# Sheet1.net
KiCad netlist of a schematic drawn in Altium Designer
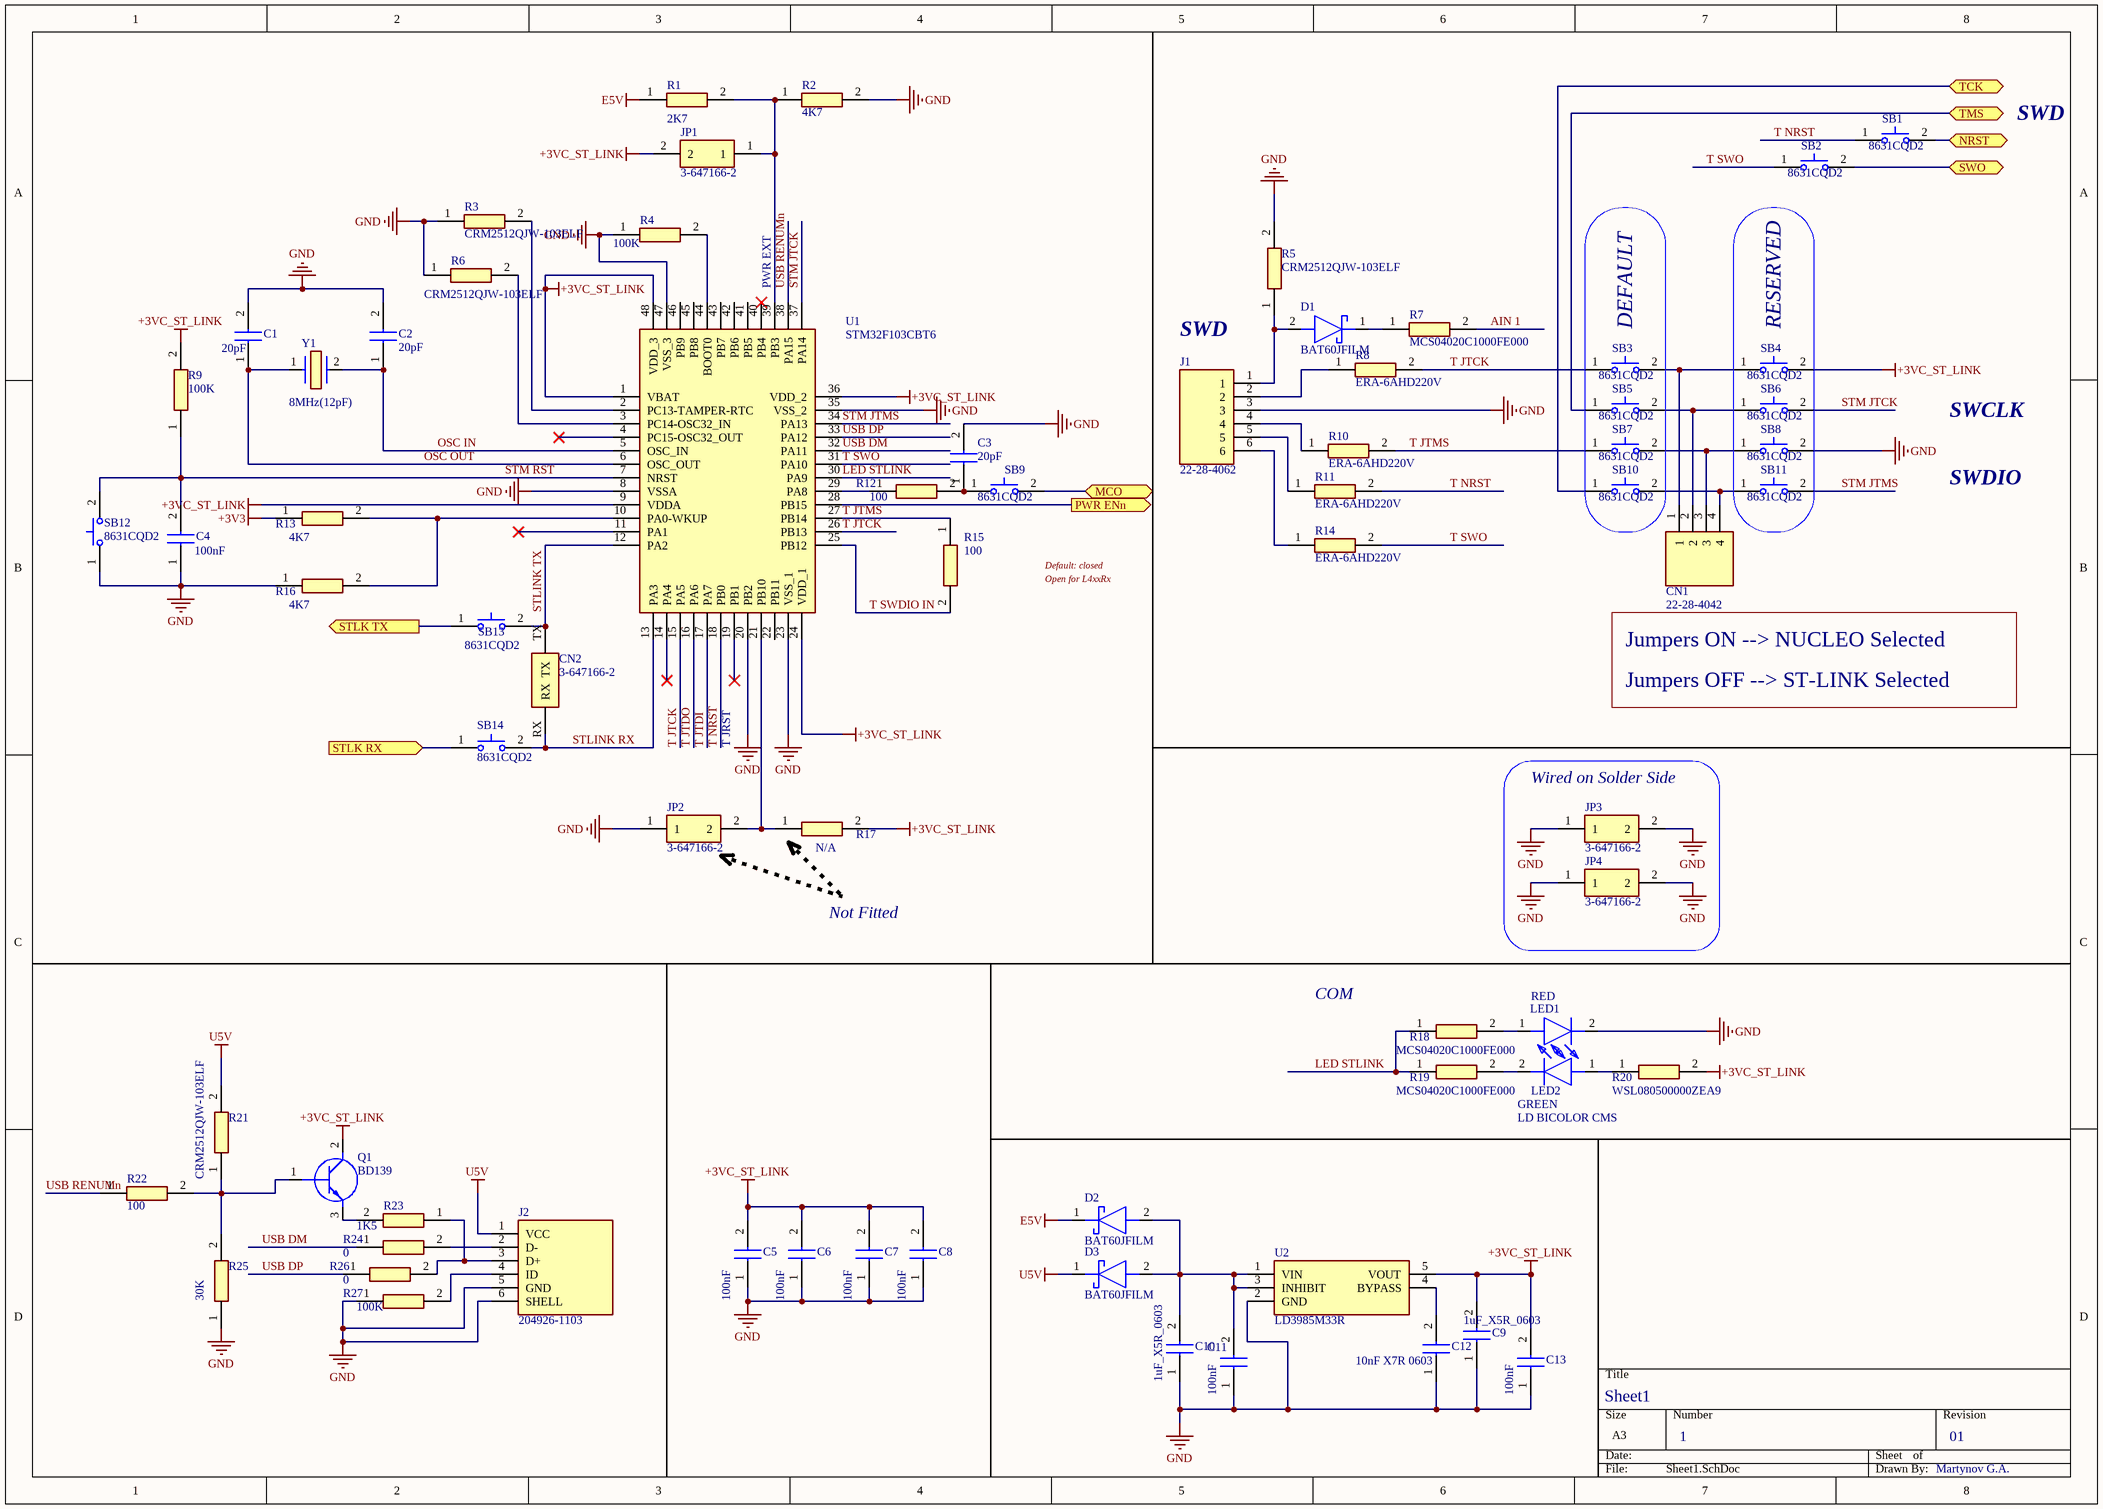
[diagram p0: Sheet1.SchDoc]

(export (version "E")
  (design (tool "Eeschema 10.0.6"))
  (components
    (comp (ref "C1")
      (value "20pF")
      (footprint "SamacSys:C1206")
      (description "Capacitor")
      (fields (field (name "MANUFACTURER_PART_NUMBER") "C1206C200KCGACTU"))
      (libsource (lib "*") (part "C1206C200KCGACTU"))
    )
    (comp (ref "C2")
      (value "20pF")
      (footprint "SamacSys:C1206")
      (description "Capacitor")
      (fields (field (name "MANUFACTURER_PART_NUMBER") "C1206C200KCGACTU"))
      (libsource (lib "*") (part "C1206C200KCGACTU"))
    )
    (comp (ref "C3")
      (value "20pF")
      (footprint "SamacSys:C1206")
      (description "Capacitor")
      (fields (field (name "MANUFACTURER_PART_NUMBER") "C1206C200KCGACTU"))
      (libsource (lib "*") (part "C1206C200KCGACTU"))
    )
    (comp (ref "C4")
      (value "100nF")
      (footprint "SamacSys:CAPC1608X90N")
      (description "Capacitor")
      (fields
        (field (name "MANUFACTURER_PART_NUMBER") "06035C104K4T4A")
        (field (name "MOUSER PART NUMBER") "581-06035C104K4T4A")
      )
      (libsource (lib "*") (part "06035C104K4T4A"))
    )
    (comp (ref "C5")
      (value "100nF")
      (footprint "SamacSys:CAPC1608X90N")
      (description "Capacitor")
      (fields
        (field (name "MANUFACTURER_PART_NUMBER") "06035C104K4T4A")
        (field (name "MOUSER PART NUMBER") "581-06035C104K4T4A")
      )
      (libsource (lib "*") (part "06035C104K4T4A"))
    )
    (comp (ref "C6")
      (value "100nF")
      (footprint "SamacSys:CAPC1608X90N")
      (description "Capacitor")
      (fields
        (field (name "MANUFACTURER_PART_NUMBER") "06035C104K4T4A")
        (field (name "MOUSER PART NUMBER") "581-06035C104K4T4A")
      )
      (libsource (lib "*") (part "06035C104K4T4A"))
    )
    (comp (ref "C7")
      (value "100nF")
      (footprint "SamacSys:CAPC1608X90N")
      (description "Capacitor")
      (fields
        (field (name "MANUFACTURER_PART_NUMBER") "06035C104K4T4A")
        (field (name "MOUSER PART NUMBER") "581-06035C104K4T4A")
      )
      (libsource (lib "*") (part "06035C104K4T4A"))
    )
    (comp (ref "C8")
      (value "100nF")
      (footprint "SamacSys:CAPC1608X90N")
      (description "Capacitor")
      (fields
        (field (name "MANUFACTURER_PART_NUMBER") "06035C104K4T4A")
        (field (name "MOUSER PART NUMBER") "581-06035C104K4T4A")
      )
      (libsource (lib "*") (part "06035C104K4T4A"))
    )
    (comp (ref "C9")
      (value "1uF_X5R_0603")
      (footprint "SamacSys:MAJx16")
      (description "Capacitor")
      (fields (field (name "MANUFACTURER_PART_NUMBER") "MAJCT168BB7105KTEA01"))
      (libsource (lib "*") (part "MAJCT168BB7105KTEA01"))
    )
    (comp (ref "C10")
      (value "1uF_X5R_0603")
      (footprint "SamacSys:MAJx16")
      (description "Capacitor")
      (fields (field (name "MANUFACTURER_PART_NUMBER") "MAJCT168BB7105KTEA01"))
      (libsource (lib "*") (part "MAJCT168BB7105KTEA01"))
    )
    (comp (ref "C11")
      (value "100nF")
      (footprint "SamacSys:CAPC1608X90N")
      (description "Capacitor")
      (fields
        (field (name "MANUFACTURER_PART_NUMBER") "06035C104K4T4A")
        (field (name "MOUSER PART NUMBER") "581-06035C104K4T4A")
      )
      (libsource (lib "*") (part "06035C104K4T4A"))
    )
    (comp (ref "C12")
      (value "10nF X7R 0603")
      (footprint "SamacSys:CAPC3316X145N")
      (description "Capacitor")
      (fields
        (field (name "MANUFACTURER_PART_NUMBER") "KGM31GCG2J103JU")
        (field (name "MOUSER PART NUMBER") "581-KGM31GCG2J103JU")
      )
      (libsource (lib "*") (part "KGM31GCG2J103JU"))
    )
    (comp (ref "C13")
      (value "100nF")
      (footprint "SamacSys:CAPC1608X90N")
      (description "Capacitor")
      (fields
        (field (name "MANUFACTURER_PART_NUMBER") "06035C104K4T4A")
        (field (name "MOUSER PART NUMBER") "581-06035C104K4T4A")
      )
      (libsource (lib "*") (part "06035C104K4T4A"))
    )
    (comp (ref "CN1")
      (value "22-28-4042")
      (footprint "SamacSys:HDRV4W66P0X254_1X4_1016X249X1003P")
      (description "Connector")
      (fields (field (name "MOUSER PART NUMBER") "538-22-28-4042"))
      (libsource (lib "*") (part "22-28-4042"))
    )
    (comp (ref "CN2")
      (value "3-647166-2")
      (footprint "SamacSys:36471662")
      (description "Connector")
      (fields (field (name "MOUSER PART NUMBER") "571-3-647166-2"))
      (libsource (lib "") (part "3-647166-2_2"))
    )
    (comp (ref "D1")
      (value "BAT60JFILM")
      (footprint "SamacSys:SOD2513X117N")
      (description "Schottky Diode")
      (fields (field (name "MOUSER PART NUMBER") "511-BAT60JFILM"))
      (libsource (lib "*") (part "BAT60JFILM"))
    )
    (comp (ref "D2")
      (value "BAT60JFILM")
      (footprint "SamacSys:SOD2513X117N")
      (description "Schottky Diode")
      (fields (field (name "MOUSER PART NUMBER") "511-BAT60JFILM"))
      (libsource (lib "*") (part "BAT60JFILM"))
    )
    (comp (ref "D3")
      (value "BAT60JFILM")
      (footprint "SamacSys:SOD2513X117N")
      (description "Schottky Diode")
      (fields (field (name "MOUSER PART NUMBER") "511-BAT60JFILM"))
      (libsource (lib "*") (part "BAT60JFILM"))
    )
    (comp (ref "J1")
      (value "22-28-4062")
      (footprint "SamacSys:HDRV6W66P0X254_1X6_1524X249X838P")
      (description "Connector")
      (fields (field (name "MOUSER PART NUMBER") "538-22-28-4062"))
      (libsource (lib "*") (part "22-28-4062"))
    )
    (comp (ref "J2")
      (value "204926-1103")
      (footprint "SamacSys:2049261103")
      (description "Connector")
      (fields (field (name "MOUSER PART NUMBER") "538-204926-1103"))
      (libsource (lib "*") (part "204926-1103"))
    )
    (comp (ref "JP1")
      (value "3-647166-2")
      (footprint "SamacSys:36471662")
      (description "Connector")
      (fields (field (name "MOUSER PART NUMBER") "571-3-647166-2"))
      (libsource (lib "") (part "3-647166-2_1"))
    )
    (comp (ref "JP2")
      (value "3-647166-2")
      (footprint "SamacSys:36471662")
      (description "Connector")
      (fields (field (name "MOUSER PART NUMBER") "571-3-647166-2"))
      (libsource (lib "JP") (part "3-647166-2"))
    )
    (comp (ref "JP3")
      (value "3-647166-2")
      (footprint "SamacSys:36471662")
      (description "Connector")
      (fields (field (name "MOUSER PART NUMBER") "571-3-647166-2"))
      (libsource (lib "JP") (part "3-647166-2"))
    )
    (comp (ref "JP4")
      (value "3-647166-2")
      (footprint "SamacSys:36471662")
      (description "Connector")
      (fields (field (name "MOUSER PART NUMBER") "571-3-647166-2"))
      (libsource (lib "JP") (part "3-647166-2"))
    )
    (comp (ref "LED1")
      (value "RED")
      (footprint "SamacSys:C4SMARGYCS4V1BB1")
      (description "LED")
      (fields
        (field (name "MANUFACTURER_PART_NUMBER") "C4SMA-RGY-CS4V1BB1")
        (field (name "MOUSER PART NUMBER") "941-C4SMARGYCS4V1BB1")
      )
      (libsource (lib "*") (part "C4SMA-RGY-CS4V1BB1"))
    )
    (comp (ref "LED2")
      (value "GREEN")
      (footprint "SamacSys:C4SMAGGYCU2W37A1")
      (description "LED")
      (fields
        (field (name "MANUFACTURER_PART_NUMBER") "C4SMA-GGY-CU2W37A1")
        (field (name "MOUSER PART NUMBER") "941-C4SMAGGYCU2W37A1")
      )
      (libsource (lib "*") (part "C4SMA-GGY-CU2W37A1"))
    )
    (comp (ref "Q1")
      (value "BD139")
      (footprint "SamacSys:TO254P290X760X1320-3P")
      (description "Transistor BJT NPN")
      (fields (field (name "MOUSER PART NUMBER") "511-BD139"))
      (libsource (lib "*") (part "BD139"))
    )
    (comp (ref "R1")
      (value "2K7")
      (footprint "SamacSys:RESC3225X70N")
      (description "Resistor")
      (fields
        (field (name "MANUFACTURER_PART_NUMBER") "CRCW12102K70FKEAHP")
        (field (name "MOUSER PART NUMBER") "71-CRCW12102K70FKEAH")
      )
      (libsource (lib "*") (part "CRCW12102K70FKEAHP"))
    )
    (comp (ref "R2")
      (value "4K7")
      (footprint "SamacSys:RESC1005X37N")
      (description "Resistor")
      (fields
        (field (name "MANUFACTURER_PART_NUMBER") "MCS04020D4701BE000")
        (field (name "MOUSER PART NUMBER") "594-MCS04020D4701BE0")
      )
      (libsource (lib "*") (part "MCS04020D4701BE000"))
    )
    (comp (ref "R3")
      (value "CRM2512QJW-103ELF")
      (footprint "SamacSys:RESC6331X80N")
      (description "Resistor")
      (fields (field (name "MOUSER PART NUMBER") "652-CRM2512QJW-103E"))
      (libsource (lib "*") (part "CRM2512QJW-103ELF"))
    )
    (comp (ref "R4")
      (value "100K")
      (footprint "SamacSys:RESC1005X40N")
      (description "Resistor")
      (fields
        (field (name "MANUFACTURER_PART_NUMBER") "SFR01MZPF1003")
        (field (name "MOUSER PART NUMBER") "755-SFR01MZPF1003")
      )
      (libsource (lib "") (part "SFR01MZPF1003_1"))
    )
    (comp (ref "R5")
      (value "CRM2512QJW-103ELF")
      (footprint "SamacSys:RESC6331X80N")
      (description "Resistor")
      (fields (field (name "MOUSER PART NUMBER") "652-CRM2512QJW-103E"))
      (libsource (lib "") (part "CRM2512QJW-103ELF_1"))
    )
    (comp (ref "R6")
      (value "CRM2512QJW-103ELF")
      (footprint "SamacSys:RESC6331X80N")
      (description "Resistor")
      (fields (field (name "MOUSER PART NUMBER") "652-CRM2512QJW-103E"))
      (libsource (lib "*") (part "CRM2512QJW-103ELF"))
    )
    (comp (ref "R7")
      (value "MCS04020C1000FE000")
      (footprint "SamacSys:RESC1005X37N")
      (description "Resistor")
      (fields (field (name "MOUSER PART NUMBER") "594-MCS04020C1000FE0"))
      (libsource (lib "") (part "MCS04020C1000FE000_1"))
    )
    (comp (ref "R8")
      (value "ERA-6AHD220V")
      (footprint "SamacSys:ERA6AEB1020V")
      (description "Resistor")
      (fields (field (name "MOUSER PART NUMBER") "667-ERA-6AHD220V"))
      (libsource (lib "*") (part "ERA-6AHD220V"))
    )
    (comp (ref "R9")
      (value "100K")
      (footprint "SamacSys:RESC1005X40N")
      (description "Resistor")
      (fields
        (field (name "MANUFACTURER_PART_NUMBER") "SFR01MZPF1003")
        (field (name "MOUSER PART NUMBER") "755-SFR01MZPF1003")
      )
      (libsource (lib "*") (part "SFR01MZPF1003"))
    )
    (comp (ref "R10")
      (value "ERA-6AHD220V")
      (footprint "SamacSys:ERA6AEB1020V")
      (description "Resistor")
      (fields (field (name "MOUSER PART NUMBER") "667-ERA-6AHD220V"))
      (libsource (lib "*") (part "ERA-6AHD220V"))
    )
    (comp (ref "R11")
      (value "ERA-6AHD220V")
      (footprint "SamacSys:ERA6AEB1020V")
      (description "Resistor")
      (fields (field (name "MOUSER PART NUMBER") "667-ERA-6AHD220V"))
      (libsource (lib "*") (part "ERA-6AHD220V"))
    )
    (comp (ref "R12")
      (value "100")
      (footprint "SamacSys:RESC1005X37N")
      (description "Resistor")
      (fields
        (field (name "MANUFACTURER_PART_NUMBER") "MCS04020C1000FE000")
        (field (name "MOUSER PART NUMBER") "594-MCS04020C1000FE0")
      )
      (libsource (lib "") (part "MCS04020C1000FE000_1"))
    )
    (comp (ref "R13")
      (value "4K7")
      (footprint "SamacSys:RESC1005X37N")
      (description "Resistor")
      (fields
        (field (name "MANUFACTURER_PART_NUMBER") "MCS04020D4701BE000")
        (field (name "MOUSER PART NUMBER") "594-MCS04020D4701BE0")
      )
      (libsource (lib "*") (part "MCS04020D4701BE000"))
    )
    (comp (ref "R14")
      (value "ERA-6AHD220V")
      (footprint "SamacSys:ERA6AEB1020V")
      (description "Resistor")
      (fields (field (name "MOUSER PART NUMBER") "667-ERA-6AHD220V"))
      (libsource (lib "*") (part "ERA-6AHD220V"))
    )
    (comp (ref "R15")
      (value "100")
      (footprint "SamacSys:RESC1005X37N")
      (description "Resistor")
      (fields
        (field (name "MANUFACTURER_PART_NUMBER") "MCS04020C1000FE000")
        (field (name "MOUSER PART NUMBER") "594-MCS04020C1000FE0")
      )
      (libsource (lib "*") (part "MCS04020C1000FE000"))
    )
    (comp (ref "R16")
      (value "4K7")
      (footprint "SamacSys:RESC1005X37N")
      (description "Resistor")
      (fields
        (field (name "MANUFACTURER_PART_NUMBER") "MCS04020D4701BE000")
        (field (name "MOUSER PART NUMBER") "594-MCS04020D4701BE0")
      )
      (libsource (lib "*") (part "MCS04020D4701BE000"))
    )
    (comp (ref "R17")
      (value "N/A")
      (footprint "SamacSys:RESC2013X84N")
      (description "Resistor")
      (fields
        (field (name "MANUFACTURER_PART_NUMBER") "WSL080500000ZEA9")
        (field (name "MOUSER PART NUMBER") "71-WSL080500000ZEA9")
      )
      (libsource (lib "*") (part "WSL080500000ZEA9"))
    )
    (comp (ref "R18")
      (value "MCS04020C1000FE000")
      (footprint "SamacSys:RESC1005X37N")
      (description "Resistor")
      (fields (field (name "MOUSER PART NUMBER") "594-MCS04020C1000FE0"))
      (libsource (lib "") (part "MCS04020C1000FE000_1"))
    )
    (comp (ref "R19")
      (value "MCS04020C1000FE000")
      (footprint "SamacSys:RESC1005X37N")
      (description "Resistor")
      (fields (field (name "MOUSER PART NUMBER") "594-MCS04020C1000FE0"))
      (libsource (lib "") (part "MCS04020C1000FE000_1"))
    )
    (comp (ref "R20")
      (value "WSL080500000ZEA9")
      (footprint "SamacSys:RESC2013X84N")
      (description "Resistor")
      (fields (field (name "MOUSER PART NUMBER") "71-WSL080500000ZEA9"))
      (libsource (lib "*") (part "WSL080500000ZEA9"))
    )
    (comp (ref "R21")
      (value "CRM2512QJW-103ELF")
      (footprint "SamacSys:RESC6331X80N")
      (description "Resistor")
      (fields (field (name "MOUSER PART NUMBER") "652-CRM2512QJW-103E"))
      (libsource (lib "") (part "CRM2512QJW-103ELF_1"))
    )
    (comp (ref "R22")
      (value "100")
      (footprint "SamacSys:RESC1005X37N")
      (description "Resistor")
      (fields
        (field (name "MANUFACTURER_PART_NUMBER") "MCS04020C1000FE000")
        (field (name "MOUSER PART NUMBER") "594-MCS04020C1000FE0")
      )
      (libsource (lib "") (part "MCS04020C1000FE000_1"))
    )
    (comp (ref "R23")
      (value "1K5")
      (footprint "SamacSys:RESC3116X65N")
      (description "Resistor")
      (fields
        (field (name "MANUFACTURER_PART_NUMBER") "CRCW12061K50FKEAHP")
        (field (name "MOUSER PART NUMBER") "71-CRCW12061K50FKEAH")
      )
      (libsource (lib "*") (part "CRCW12061K50FKEAHP"))
    )
    (comp (ref "R24")
      (value "0")
      (footprint "SamacSys:RESC2013X84N")
      (description "Resistor")
      (fields
        (field (name "MANUFACTURER_PART_NUMBER") "WSL080500000ZEA9")
        (field (name "MOUSER PART NUMBER") "71-WSL080500000ZEA9")
      )
      (libsource (lib "*") (part "WSL080500000ZEA9"))
    )
    (comp (ref "R25")
      (value "30K")
      (footprint "SamacSys:RESC2012X55N")
      (description "Resistor")
      (fields (field (name "MANUFACTURER_PART_NUMBER") "TNPW080536K0BEEA"))
      (libsource (lib "JP2") (part "TNPW080536K0BEEA"))
    )
    (comp (ref "R26")
      (value "0")
      (footprint "SamacSys:RESC2013X84N")
      (description "Resistor")
      (fields
        (field (name "MANUFACTURER_PART_NUMBER") "WSL080500000ZEA9")
        (field (name "MOUSER PART NUMBER") "71-WSL080500000ZEA9")
      )
      (libsource (lib "*") (part "WSL080500000ZEA9"))
    )
    (comp (ref "R27")
      (value "100K")
      (footprint "SamacSys:RESC1005X40N")
      (description "Resistor")
      (fields
        (field (name "MANUFACTURER_PART_NUMBER") "SFR01MZPF1003")
        (field (name "MOUSER PART NUMBER") "755-SFR01MZPF1003")
      )
      (libsource (lib "JP2") (part "SFR01MZPF1003"))
    )
    (comp (ref "SB1")
      (value "8631CQD2")
      (footprint "SamacSys:8631CQD2")
      (description "Switch (2-Pin Push)")
      (fields (field (name "MOUSER PART NUMBER") "611-8631-261"))
      (libsource (lib "PB") (part "8631CQD2"))
    )
    (comp (ref "SB2")
      (value "8631CQD2")
      (footprint "SamacSys:8631CQD2")
      (description "Switch (2-Pin Push)")
      (fields (field (name "MOUSER PART NUMBER") "611-8631-261"))
      (libsource (lib "PB") (part "8631CQD2"))
    )
    (comp (ref "SB3")
      (value "8631CQD2")
      (footprint "SamacSys:8631CQD2")
      (description "Switch (2-Pin Push)")
      (fields (field (name "MOUSER PART NUMBER") "611-8631-261"))
      (libsource (lib "PB") (part "8631CQD2"))
    )
    (comp (ref "SB4")
      (value "8631CQD2")
      (footprint "SamacSys:8631CQD2")
      (description "Switch (2-Pin Push)")
      (fields (field (name "MOUSER PART NUMBER") "611-8631-261"))
      (libsource (lib "PB") (part "8631CQD2"))
    )
    (comp (ref "SB5")
      (value "8631CQD2")
      (footprint "SamacSys:8631CQD2")
      (description "Switch (2-Pin Push)")
      (fields (field (name "MOUSER PART NUMBER") "611-8631-261"))
      (libsource (lib "PB") (part "8631CQD2"))
    )
    (comp (ref "SB6")
      (value "8631CQD2")
      (footprint "SamacSys:8631CQD2")
      (description "Switch (2-Pin Push)")
      (fields (field (name "MOUSER PART NUMBER") "611-8631-261"))
      (libsource (lib "PB") (part "8631CQD2"))
    )
    (comp (ref "SB7")
      (value "8631CQD2")
      (footprint "SamacSys:8631CQD2")
      (description "Switch (2-Pin Push)")
      (fields (field (name "MOUSER PART NUMBER") "611-8631-261"))
      (libsource (lib "PB") (part "8631CQD2"))
    )
    (comp (ref "SB8")
      (value "8631CQD2")
      (footprint "SamacSys:8631CQD2")
      (description "Switch (2-Pin Push)")
      (fields (field (name "MOUSER PART NUMBER") "611-8631-261"))
      (libsource (lib "PB") (part "8631CQD2"))
    )
    (comp (ref "SB9")
      (value "8631CQD2")
      (footprint "SamacSys:8631CQD2")
      (description "Switch (2-Pin Push)")
      (fields (field (name "MOUSER PART NUMBER") "611-8631-261"))
      (libsource (lib "PB") (part "8631CQD2"))
    )
    (comp (ref "SB10")
      (value "8631CQD2")
      (footprint "SamacSys:8631CQD2")
      (description "Switch (2-Pin Push)")
      (fields (field (name "MOUSER PART NUMBER") "611-8631-261"))
      (libsource (lib "PB") (part "8631CQD2"))
    )
    (comp (ref "SB11")
      (value "8631CQD2")
      (footprint "SamacSys:8631CQD2")
      (description "Switch (2-Pin Push)")
      (fields (field (name "MOUSER PART NUMBER") "611-8631-261"))
      (libsource (lib "PB") (part "8631CQD2"))
    )
    (comp (ref "SB12")
      (value "8631CQD2")
      (footprint "SamacSys:8631CQD2")
      (description "Switch (2-Pin Push)")
      (fields (field (name "MOUSER PART NUMBER") "611-8631-261"))
      (libsource (lib "PB") (part "8631CQD2"))
    )
    (comp (ref "SB13")
      (value "8631CQD2")
      (footprint "SamacSys:8631CQD2")
      (description "Switch (2-Pin Push)")
      (fields (field (name "MOUSER PART NUMBER") "611-8631-261"))
      (libsource (lib "PB") (part "8631CQD2"))
    )
    (comp (ref "SB14")
      (value "8631CQD2")
      (footprint "SamacSys:8631CQD2")
      (description "Switch (2-Pin Push)")
      (fields (field (name "MOUSER PART NUMBER") "611-8631-261"))
      (libsource (lib "PB") (part "8631CQD2"))
    )
    (comp (ref "U1")
      (value "STM32F103CBT6")
      (footprint "SamacSys:QFP50P900X900X160-48N")
      (description "Integrated Circuit")
      (fields (field (name "MOUSER PART NUMBER") "511-STM32F103CBT6"))
      (libsource (lib "STM32F103CBT6") (part "STM32F103CBT6"))
    )
    (comp (ref "U2")
      (value "LD3985M33R")
      (footprint "SamacSys:SOT95P280X145-5N")
      (description "Integrated Circuit")
      (fields (field (name "MOUSER PART NUMBER") "511-LD3985M33R"))
      (libsource (lib "*") (part "LD3985M33R"))
    )
    (comp (ref "Y1")
      (value "8MHz(12pF)")
      (footprint "SamacSys:ECS80125PXGMTR")
      (description "Crystal or Oscillator")
      (fields
        (field (name "MANUFACTURER_PART_NUMBER") "ECS-80-12-5PX-GM-TR")
        (field (name "MOUSER PART NUMBER") "520-80-12-5PX-GM-TR")
      )
      (libsource (lib "*") (part "ECS-80-12-5PX-GM-TR"))
    )
  )
  (nets
    (net (code "1") (name "+3V3") (class "Default")
      (node (ref "R13") (pin "1") (pinfunction "1_1") (pintype "passive"))
    )
    (net (code "2") (name "+3VC_ST_LINK") (class "Default")
      (node (ref "C13") (pin "2") (pinfunction "2_2") (pintype "passive"))
      (node (ref "C5") (pin "2") (pinfunction "2_2") (pintype "passive"))
      (node (ref "C6") (pin "2") (pinfunction "2_2") (pintype "passive"))
      (node (ref "C7") (pin "2") (pinfunction "2_2") (pintype "passive"))
      (node (ref "C8") (pin "2") (pinfunction "2_2") (pintype "passive"))
      (node (ref "C9") (pin "2") (pinfunction "2_2") (pintype "passive"))
      (node (ref "JP1") (pin "2") (pinfunction "2_2") (pintype "passive"))
      (node (ref "Q1") (pin "2") (pinfunction "C_2") (pintype "passive"))
      (node (ref "R17") (pin "2") (pinfunction "2_2") (pintype "passive"))
      (node (ref "R20") (pin "2") (pinfunction "2_2") (pintype "passive"))
      (node (ref "R9") (pin "2") (pinfunction "2_2") (pintype "passive"))
      (node (ref "SB4") (pin "2") (pinfunction "N.O._2_2") (pintype "passive"))
      (node (ref "U1") (pin "1") (pinfunction "VBAT_1") (pintype "passive"))
      (node (ref "U1") (pin "24") (pinfunction "VDD_1_24") (pintype "passive"))
      (node (ref "U1") (pin "36") (pinfunction "VDD_2_36") (pintype "passive"))
      (node (ref "U1") (pin "48") (pinfunction "VDD_3_48") (pintype "passive"))
      (node (ref "U1") (pin "9") (pinfunction "VDDA_9") (pintype "passive"))
      (node (ref "U2") (pin "5") (pinfunction "VOUT_5") (pintype "passive"))
    )
    (net (code "3") (name "/AIN 1") (class "Default")
      (node (ref "R7") (pin "2") (pinfunction "2_2") (pintype "passive"))
    )
    (net (code "5") (name "/LED STLINK") (class "Default")
      (node (ref "R18") (pin "1") (pinfunction "1_1") (pintype "passive"))
      (node (ref "R19") (pin "1") (pinfunction "1_1") (pintype "passive"))
      (node (ref "U1") (pin "30") (pinfunction "PA9_30") (pintype "passive"))
    )
    (net (code "6") (name "/MCO") (class "Default")
      (node (ref "SB9") (pin "2") (pinfunction "N.O._2_2") (pintype "passive"))
    )
    (net (code "7") (name "/NRST") (class "Default")
      (node (ref "SB1") (pin "2") (pinfunction "N.O._2_2") (pintype "passive"))
    )
    (net (code "8") (name "/OSC IN") (class "Default")
      (node (ref "C2") (pin "1") (pinfunction "1_1") (pintype "passive"))
      (node (ref "U1") (pin "5") (pinfunction "OSC_IN_5") (pintype "passive"))
      (node (ref "Y1") (pin "2") (pinfunction "2_2") (pintype "passive"))
    )
    (net (code "9") (name "/OSC OUT") (class "Default")
      (node (ref "C1") (pin "1") (pinfunction "1_1") (pintype "passive"))
      (node (ref "U1") (pin "6") (pinfunction "OSC_OUT_6") (pintype "passive"))
      (node (ref "Y1") (pin "1") (pinfunction "1_1") (pintype "passive"))
    )
    (net (code "11") (name "/PWR ENn") (class "Default")
      (node (ref "U1") (pin "28") (pinfunction "PB15_28") (pintype "passive"))
    )
    (net (code "12") (name "/STLINK RX") (class "Default")
      (node (ref "CN2") (pin "RX") (pinfunction "RX_RX") (pintype "passive"))
      (node (ref "SB14") (pin "2") (pinfunction "N.O._2_2") (pintype "passive"))
      (node (ref "U1") (pin "13") (pinfunction "PA3_13") (pintype "passive"))
    )
    (net (code "13") (name "/STLINK TX") (class "Default")
      (node (ref "CN2") (pin "TX") (pinfunction "TX_TX") (pintype "passive"))
      (node (ref "SB13") (pin "2") (pinfunction "N.O._2_2") (pintype "passive"))
      (node (ref "U1") (pin "12") (pinfunction "PA2_12") (pintype "passive"))
    )
    (net (code "14") (name "/STLK RX") (class "Default")
      (node (ref "SB14") (pin "1") (pinfunction "N.O._1_1") (pintype "passive"))
    )
    (net (code "15") (name "/STLK TX") (class "Default")
      (node (ref "SB13") (pin "1") (pinfunction "N.O._1_1") (pintype "passive"))
    )
    (net (code "16") (name "/STM JTCK") (class "Default")
      (node (ref "SB6") (pin "2") (pinfunction "N.O._2_2") (pintype "passive"))
      (node (ref "U1") (pin "37") (pinfunction "PA14_37") (pintype "passive"))
    )
    (net (code "17") (name "/STM JTMS") (class "Default")
      (node (ref "SB11") (pin "2") (pinfunction "N.O._2_2") (pintype "passive"))
      (node (ref "U1") (pin "34") (pinfunction "PA13_34") (pintype "passive"))
    )
    (net (code "18") (name "/STM RST") (class "Default")
      (node (ref "C4") (pin "2") (pinfunction "2_2") (pintype "passive"))
      (node (ref "R9") (pin "1") (pinfunction "1_1") (pintype "passive"))
      (node (ref "SB12") (pin "2") (pinfunction "N.O._2_2") (pintype "passive"))
      (node (ref "U1") (pin "7") (pinfunction "NRST_7") (pintype "passive"))
    )
    (net (code "19") (name "/SWO") (class "Default")
      (node (ref "SB2") (pin "2") (pinfunction "N.O._2_2") (pintype "passive"))
    )
    (net (code "20") (name "/T JTCK") (class "Default")
      (node (ref "R8") (pin "2") (pinfunction "2_2") (pintype "passive"))
      (node (ref "SB3") (pin "1") (pinfunction "N.O._1_1") (pintype "passive"))
      (node (ref "U1") (pin "15") (pinfunction "PA5_15") (pintype "passive"))
      (node (ref "U1") (pin "26") (pinfunction "PB13_26") (pintype "passive"))
    )
    (net (code "21") (name "/T JTDI") (class "Default")
      (node (ref "U1") (pin "17") (pinfunction "PA7_17") (pintype "passive"))
    )
    (net (code "22") (name "/T JTDO") (class "Default")
      (node (ref "U1") (pin "16") (pinfunction "PA6_16") (pintype "passive"))
    )
    (net (code "23") (name "/T JTMS") (class "Default")
      (node (ref "R10") (pin "2") (pinfunction "2_2") (pintype "passive"))
      (node (ref "R15") (pin "1") (pinfunction "1_1") (pintype "passive"))
      (node (ref "SB7") (pin "1") (pinfunction "N.O._1_1") (pintype "passive"))
      (node (ref "U1") (pin "27") (pinfunction "PB14_27") (pintype "passive"))
    )
    (net (code "24") (name "/T NRST") (class "Default")
      (node (ref "R11") (pin "2") (pinfunction "2_2") (pintype "passive"))
      (node (ref "SB1") (pin "1") (pinfunction "N.O._1_1") (pintype "passive"))
      (node (ref "U1") (pin "18") (pinfunction "PB0_18") (pintype "passive"))
    )
    (net (code "25") (name "/T SWDIO IN") (class "Default")
      (node (ref "R15") (pin "2") (pinfunction "2_2") (pintype "passive"))
      (node (ref "U1") (pin "25") (pinfunction "PB12_25") (pintype "passive"))
    )
    (net (code "26") (name "/T SWO") (class "Default")
      (node (ref "R14") (pin "2") (pinfunction "2_2") (pintype "passive"))
      (node (ref "SB2") (pin "1") (pinfunction "N.O._1_1") (pintype "passive"))
      (node (ref "U1") (pin "31") (pinfunction "PA10_31") (pintype "passive"))
    )
    (net (code "27") (name "/TCK") (class "Default")
      (node (ref "SB10") (pin "1") (pinfunction "N.O._1_1") (pintype "passive"))
    )
    (net (code "28") (name "/TMS") (class "Default")
      (node (ref "SB5") (pin "1") (pinfunction "N.O._1_1") (pintype "passive"))
    )
    (net (code "29") (name "/USB DM") (class "Default")
      (node (ref "R24") (pin "1") (pinfunction "1_1") (pintype "passive"))
      (node (ref "U1") (pin "32") (pinfunction "PA11_32") (pintype "passive"))
    )
    (net (code "30") (name "/USB DP") (class "Default")
      (node (ref "R26") (pin "1") (pinfunction "1_1") (pintype "passive"))
      (node (ref "U1") (pin "33") (pinfunction "PA12_33") (pintype "passive"))
    )
    (net (code "31") (name "/USB RENUMn") (class "Default")
      (node (ref "R22") (pin "1") (pinfunction "1_1") (pintype "passive"))
      (node (ref "U1") (pin "38") (pinfunction "PA15_38") (pintype "passive"))
    )
    (net (code "32") (name "E5V") (class "Default")
      (node (ref "D2") (pin "1") (pinfunction "K_1") (pintype "passive"))
      (node (ref "R1") (pin "1") (pinfunction "1_1") (pintype "passive"))
    )
    (net (code "33") (name "GND") (class "Default")
      (node (ref "C1") (pin "2") (pinfunction "2_2") (pintype "passive"))
      (node (ref "C10") (pin "1") (pinfunction "1_1") (pintype "passive"))
      (node (ref "C11") (pin "1") (pinfunction "1_1") (pintype "passive"))
      (node (ref "C12") (pin "1") (pinfunction "1_1") (pintype "passive"))
      (node (ref "C13") (pin "1") (pinfunction "1_1") (pintype "passive"))
      (node (ref "C2") (pin "2") (pinfunction "2_2") (pintype "passive"))
      (node (ref "C3") (pin "2") (pinfunction "2_2") (pintype "passive"))
      (node (ref "C4") (pin "1") (pinfunction "1_1") (pintype "passive"))
      (node (ref "C5") (pin "1") (pinfunction "1_1") (pintype "passive"))
      (node (ref "C6") (pin "1") (pinfunction "1_1") (pintype "passive"))
      (node (ref "C7") (pin "1") (pinfunction "1_1") (pintype "passive"))
      (node (ref "C8") (pin "1") (pinfunction "1_1") (pintype "passive"))
      (node (ref "C9") (pin "1") (pinfunction "1_1") (pintype "passive"))
      (node (ref "J1") (pin "3") (pinfunction "3_3") (pintype "passive"))
      (node (ref "J2") (pin "5") (pinfunction "GND_5") (pintype "passive"))
      (node (ref "J2") (pin "6") (pinfunction "SHELL_6") (pintype "passive"))
      (node (ref "JP2") (pin "1") (pinfunction "1_1") (pintype "passive"))
      (node (ref "JP3") (pin "1") (pinfunction "1_1") (pintype "passive"))
      (node (ref "JP3") (pin "2") (pinfunction "2_2") (pintype "passive"))
      (node (ref "JP4") (pin "1") (pinfunction "1_1") (pintype "passive"))
      (node (ref "JP4") (pin "2") (pinfunction "2_2") (pintype "passive"))
      (node (ref "LED1") (pin "2") (pinfunction "K_2") (pintype "passive"))
      (node (ref "R16") (pin "1") (pinfunction "1_1") (pintype "passive"))
      (node (ref "R2") (pin "2") (pinfunction "2_2") (pintype "passive"))
      (node (ref "R25") (pin "1") (pinfunction "1_1") (pintype "passive"))
      (node (ref "R27") (pin "1") (pinfunction "1_1") (pintype "passive"))
      (node (ref "R3") (pin "1") (pinfunction "1_1") (pintype "passive"))
      (node (ref "R4") (pin "1") (pinfunction "1_1") (pintype "passive"))
      (node (ref "R5") (pin "2") (pinfunction "2_2") (pintype "passive"))
      (node (ref "R6") (pin "1") (pinfunction "1_1") (pintype "passive"))
      (node (ref "SB12") (pin "1") (pinfunction "N.O._1_1") (pintype "passive"))
      (node (ref "SB8") (pin "2") (pinfunction "N.O._2_2") (pintype "passive"))
      (node (ref "U1") (pin "20") (pinfunction "PB2_20") (pintype "passive"))
      (node (ref "U1") (pin "23") (pinfunction "VSS_1_23") (pintype "passive"))
      (node (ref "U1") (pin "35") (pinfunction "VSS_2_35") (pintype "passive"))
      (node (ref "U1") (pin "47") (pinfunction "VSS_3_47") (pintype "passive"))
      (node (ref "U1") (pin "8") (pinfunction "VSSA_8") (pintype "passive"))
      (node (ref "U2") (pin "2") (pinfunction "GND_2") (pintype "passive"))
    )
    (net (code "34") (name "Net-(D1-A)") (class "Default")
      (node (ref "D1") (pin "2") (pinfunction "A_2") (pintype "passive"))
      (node (ref "J1") (pin "1") (pinfunction "1_1") (pintype "passive"))
      (node (ref "R5") (pin "1") (pinfunction "1_1") (pintype "passive"))
    )
    (net (code "35") (name "Net-(D1-K)") (class "Default")
      (node (ref "D1") (pin "1") (pinfunction "K_1") (pintype "passive"))
      (node (ref "R7") (pin "1") (pinfunction "1_1") (pintype "passive"))
    )
    (net (code "36") (name "Net-(D2-A)") (class "Default")
      (node (ref "C10") (pin "2") (pinfunction "2_2") (pintype "passive"))
      (node (ref "C11") (pin "2") (pinfunction "2_2") (pintype "passive"))
      (node (ref "D2") (pin "2") (pinfunction "A_2") (pintype "passive"))
      (node (ref "D3") (pin "2") (pinfunction "A_2") (pintype "passive"))
      (node (ref "U2") (pin "1") (pinfunction "VIN_1") (pintype "passive"))
      (node (ref "U2") (pin "3") (pinfunction "INHIBIT_3") (pintype "passive"))
    )
    (net (code "37") (name "Net-(J1-Pad2)") (class "Default")
      (node (ref "J1") (pin "2") (pinfunction "2_2") (pintype "passive"))
      (node (ref "R8") (pin "1") (pinfunction "1_1") (pintype "passive"))
    )
    (net (code "38") (name "Net-(J1-Pad4)") (class "Default")
      (node (ref "J1") (pin "4") (pinfunction "4_4") (pintype "passive"))
      (node (ref "R10") (pin "1") (pinfunction "1_1") (pintype "passive"))
    )
    (net (code "39") (name "Net-(J1-Pad5)") (class "Default")
      (node (ref "J1") (pin "5") (pinfunction "5_5") (pintype "passive"))
      (node (ref "R11") (pin "1") (pinfunction "1_1") (pintype "passive"))
    )
    (net (code "40") (name "Net-(J1-Pad6)") (class "Default")
      (node (ref "J1") (pin "6") (pinfunction "6_6") (pintype "passive"))
      (node (ref "R14") (pin "1") (pinfunction "1_1") (pintype "passive"))
    )
    (net (code "41") (name "Net-(J2-D+)") (class "Default")
      (node (ref "J2") (pin "3") (pinfunction "D+_3") (pintype "passive"))
      (node (ref "R23") (pin "1") (pinfunction "1_1") (pintype "passive"))
      (node (ref "R26") (pin "2") (pinfunction "2_2") (pintype "passive"))
    )
    (net (code "42") (name "Net-(J2-D-)") (class "Default")
      (node (ref "J2") (pin "2") (pinfunction "D-_2") (pintype "passive"))
      (node (ref "R24") (pin "2") (pinfunction "2_2") (pintype "passive"))
    )
    (net (code "43") (name "Net-(J2-ID)") (class "Default")
      (node (ref "J2") (pin "4") (pinfunction "ID_4") (pintype "passive"))
      (node (ref "R27") (pin "2") (pinfunction "2_2") (pintype "passive"))
    )
    (net (code "44") (name "Net-(LED1-A)") (class "Default")
      (node (ref "LED1") (pin "1") (pinfunction "A_1") (pintype "passive"))
      (node (ref "R18") (pin "2") (pinfunction "2_2") (pintype "passive"))
    )
    (net (code "45") (name "Net-(LED2-A)") (class "Default")
      (node (ref "LED2") (pin "1") (pinfunction "A_1") (pintype "passive"))
      (node (ref "R20") (pin "1") (pinfunction "1_1") (pintype "passive"))
    )
    (net (code "46") (name "Net-(LED2-K)") (class "Default")
      (node (ref "LED2") (pin "2") (pinfunction "K_2") (pintype "passive"))
      (node (ref "R19") (pin "2") (pinfunction "2_2") (pintype "passive"))
    )
    (net (code "47") (name "Net-(Q1-B)") (class "Default")
      (node (ref "Q1") (pin "1") (pinfunction "B_1") (pintype "passive"))
      (node (ref "R21") (pin "1") (pinfunction "1_1") (pintype "passive"))
      (node (ref "R22") (pin "2") (pinfunction "2_2") (pintype "passive"))
      (node (ref "R25") (pin "2") (pinfunction "2_2") (pintype "passive"))
    )
    (net (code "48") (name "Net-(Q1-E)") (class "Default")
      (node (ref "Q1") (pin "3") (pinfunction "E_3") (pintype "passive"))
      (node (ref "R23") (pin "2") (pinfunction "2_2") (pintype "passive"))
    )
    (net (code "49") (name "Net-(SB3-N.O._2)") (class "Default")
      (node (ref "CN1") (pin "1") (pinfunction "1_1") (pintype "passive"))
      (node (ref "SB3") (pin "2") (pinfunction "N.O._2_2") (pintype "passive"))
      (node (ref "SB4") (pin "1") (pinfunction "N.O._1_1") (pintype "passive"))
    )
    (net (code "50") (name "Net-(SB5-N.O._2)") (class "Default")
      (node (ref "CN1") (pin "2") (pinfunction "2_2") (pintype "passive"))
      (node (ref "SB5") (pin "2") (pinfunction "N.O._2_2") (pintype "passive"))
      (node (ref "SB6") (pin "1") (pinfunction "N.O._1_1") (pintype "passive"))
    )
    (net (code "51") (name "Net-(SB7-N.O._2)") (class "Default")
      (node (ref "CN1") (pin "3") (pinfunction "3_3") (pintype "passive"))
      (node (ref "SB7") (pin "2") (pinfunction "N.O._2_2") (pintype "passive"))
      (node (ref "SB8") (pin "1") (pinfunction "N.O._1_1") (pintype "passive"))
    )
    (net (code "52") (name "Net-(SB9-N.O._1)") (class "Default")
      (node (ref "C3") (pin "1") (pinfunction "1_1") (pintype "passive"))
      (node (ref "R12") (pin "2") (pinfunction "2_2") (pintype "passive"))
      (node (ref "SB9") (pin "1") (pinfunction "N.O._1_1") (pintype "passive"))
    )
    (net (code "53") (name "Net-(SB10-N.O._2)") (class "Default")
      (node (ref "CN1") (pin "4") (pinfunction "4_4") (pintype "passive"))
      (node (ref "SB10") (pin "2") (pinfunction "N.O._2_2") (pintype "passive"))
      (node (ref "SB11") (pin "1") (pinfunction "N.O._1_1") (pintype "passive"))
    )
    (net (code "54") (name "Net-(U1-BOOT0)") (class "Default")
      (node (ref "R4") (pin "2") (pinfunction "2_2") (pintype "passive"))
      (node (ref "U1") (pin "44") (pinfunction "BOOT0_44") (pintype "passive"))
    )
    (net (code "55") (name "Net-(U1-PA0-WKUP)") (class "Default")
      (node (ref "R13") (pin "2") (pinfunction "2_2") (pintype "passive"))
      (node (ref "R16") (pin "2") (pinfunction "2_2") (pintype "passive"))
      (node (ref "U1") (pin "10") (pinfunction "PA0-WKUP_10") (pintype "passive"))
    )
    (net (code "56") (name "Net-(U1-PA8)") (class "Default")
      (node (ref "R12") (pin "1") (pinfunction "1_1") (pintype "passive"))
      (node (ref "U1") (pin "29") (pinfunction "PA8_29") (pintype "passive"))
    )
    (net (code "57") (name "Net-(U1-PB3)") (class "Default")
      (node (ref "JP1") (pin "1") (pinfunction "1_1") (pintype "passive"))
      (node (ref "R1") (pin "2") (pinfunction "2_2") (pintype "passive"))
      (node (ref "R2") (pin "1") (pinfunction "1_1") (pintype "passive"))
      (node (ref "U1") (pin "39") (pinfunction "PB3_39") (pintype "passive"))
    )
    (net (code "58") (name "Net-(U1-PB10)") (class "Default")
      (node (ref "JP2") (pin "2") (pinfunction "2_2") (pintype "passive"))
      (node (ref "R17") (pin "1") (pinfunction "1_1") (pintype "passive"))
      (node (ref "U1") (pin "21") (pinfunction "PB10_21") (pintype "passive"))
    )
    (net (code "59") (name "Net-(U1-PC13-TAMPER-RTC)") (class "Default")
      (node (ref "R3") (pin "2") (pinfunction "2_2") (pintype "passive"))
      (node (ref "U1") (pin "2") (pinfunction "PC13-TAMPER-RTC_2") (pintype "passive"))
    )
    (net (code "60") (name "Net-(U1-PC14-OSC32_IN)") (class "Default")
      (node (ref "R6") (pin "2") (pinfunction "2_2") (pintype "passive"))
      (node (ref "U1") (pin "3") (pinfunction "PC14-OSC32_IN_3") (pintype "passive"))
    )
    (net (code "61") (name "Net-(U2-BYPASS)") (class "Default")
      (node (ref "C12") (pin "2") (pinfunction "2_2") (pintype "passive"))
      (node (ref "U2") (pin "4") (pinfunction "BYPASS_4") (pintype "passive"))
    )
    (net (code "62") (name "U5V") (class "Default")
      (node (ref "D3") (pin "1") (pinfunction "K_1") (pintype "passive"))
      (node (ref "J2") (pin "1") (pinfunction "VCC_1") (pintype "passive"))
      (node (ref "R21") (pin "2") (pinfunction "2_2") (pintype "passive"))
    )
    (net (code "63") (name "unconnected-(J2-PadMH2)") (class "Default")
      (node (ref "J2") (pin "MH2") (pinfunction "MH2_MH2") (pintype "passive"))
    )
    (net (code "64") (name "unconnected-(J2-PadMH3)") (class "Default")
      (node (ref "J2") (pin "MH3") (pinfunction "MH3_MH3") (pintype "passive"))
    )
    (net (code "65") (name "unconnected-(J2-PadMH4)") (class "Default")
      (node (ref "J2") (pin "MH4") (pinfunction "MH4_MH4") (pintype "passive"))
    )
    (net (code "66") (name "unconnected-(J2-PadMH5)") (class "Default")
      (node (ref "J2") (pin "MH5") (pinfunction "MH5_MH5") (pintype "passive"))
    )
    (net (code "67") (name "unconnected-(J2-PadMH6)") (class "Default")
      (node (ref "J2") (pin "MH6") (pinfunction "MH6_MH6") (pintype "passive"))
    )
    (net (code "68") (name "unconnected-(U1-PA1-Pad11)") (class "Default")
      (node (ref "U1") (pin "11") (pinfunction "PA1_11") (pintype "passive+no_connect"))
    )
    (net (code "69") (name "unconnected-(U1-PA4-Pad14)") (class "Default")
      (node (ref "U1") (pin "14") (pinfunction "PA4_14") (pintype "passive+no_connect"))
    )
    (net (code "70") (name "unconnected-(U1-PB1-Pad19)") (class "Default")
      (node (ref "U1") (pin "19") (pinfunction "PB1_19") (pintype "passive+no_connect"))
    )
    (net (code "71") (name "unconnected-(U1-PB4-Pad40)") (class "Default")
      (node (ref "U1") (pin "40") (pinfunction "PB4_40") (pintype "passive+no_connect"))
    )
    (net (code "72") (name "unconnected-(U1-PB5-Pad41)") (class "Default")
      (node (ref "U1") (pin "41") (pinfunction "PB5_41") (pintype "passive"))
    )
    (net (code "73") (name "unconnected-(U1-PB6-Pad42)") (class "Default")
      (node (ref "U1") (pin "42") (pinfunction "PB6_42") (pintype "passive"))
    )
    (net (code "74") (name "unconnected-(U1-PB7-Pad43)") (class "Default")
      (node (ref "U1") (pin "43") (pinfunction "PB7_43") (pintype "passive"))
    )
    (net (code "75") (name "unconnected-(U1-PB8-Pad45)") (class "Default")
      (node (ref "U1") (pin "45") (pinfunction "PB8_45") (pintype "passive"))
    )
    (net (code "76") (name "unconnected-(U1-PB9-Pad46)") (class "Default")
      (node (ref "U1") (pin "46") (pinfunction "PB9_46") (pintype "passive"))
    )
    (net (code "77") (name "unconnected-(U1-PB11-Pad22)") (class "Default")
      (node (ref "U1") (pin "22") (pinfunction "PB11_22") (pintype "passive"))
    )
    (net (code "78") (name "unconnected-(U1-PC15-OSC32_OUT-Pad4)") (class "Default")
      (node (ref "U1") (pin "4") (pinfunction "PC15-OSC32_OUT_4") (pintype "passive+no_connect"))
    )
  )
)
